# uart.net
KiCad netlist of a schematic drawn in Altium Designer
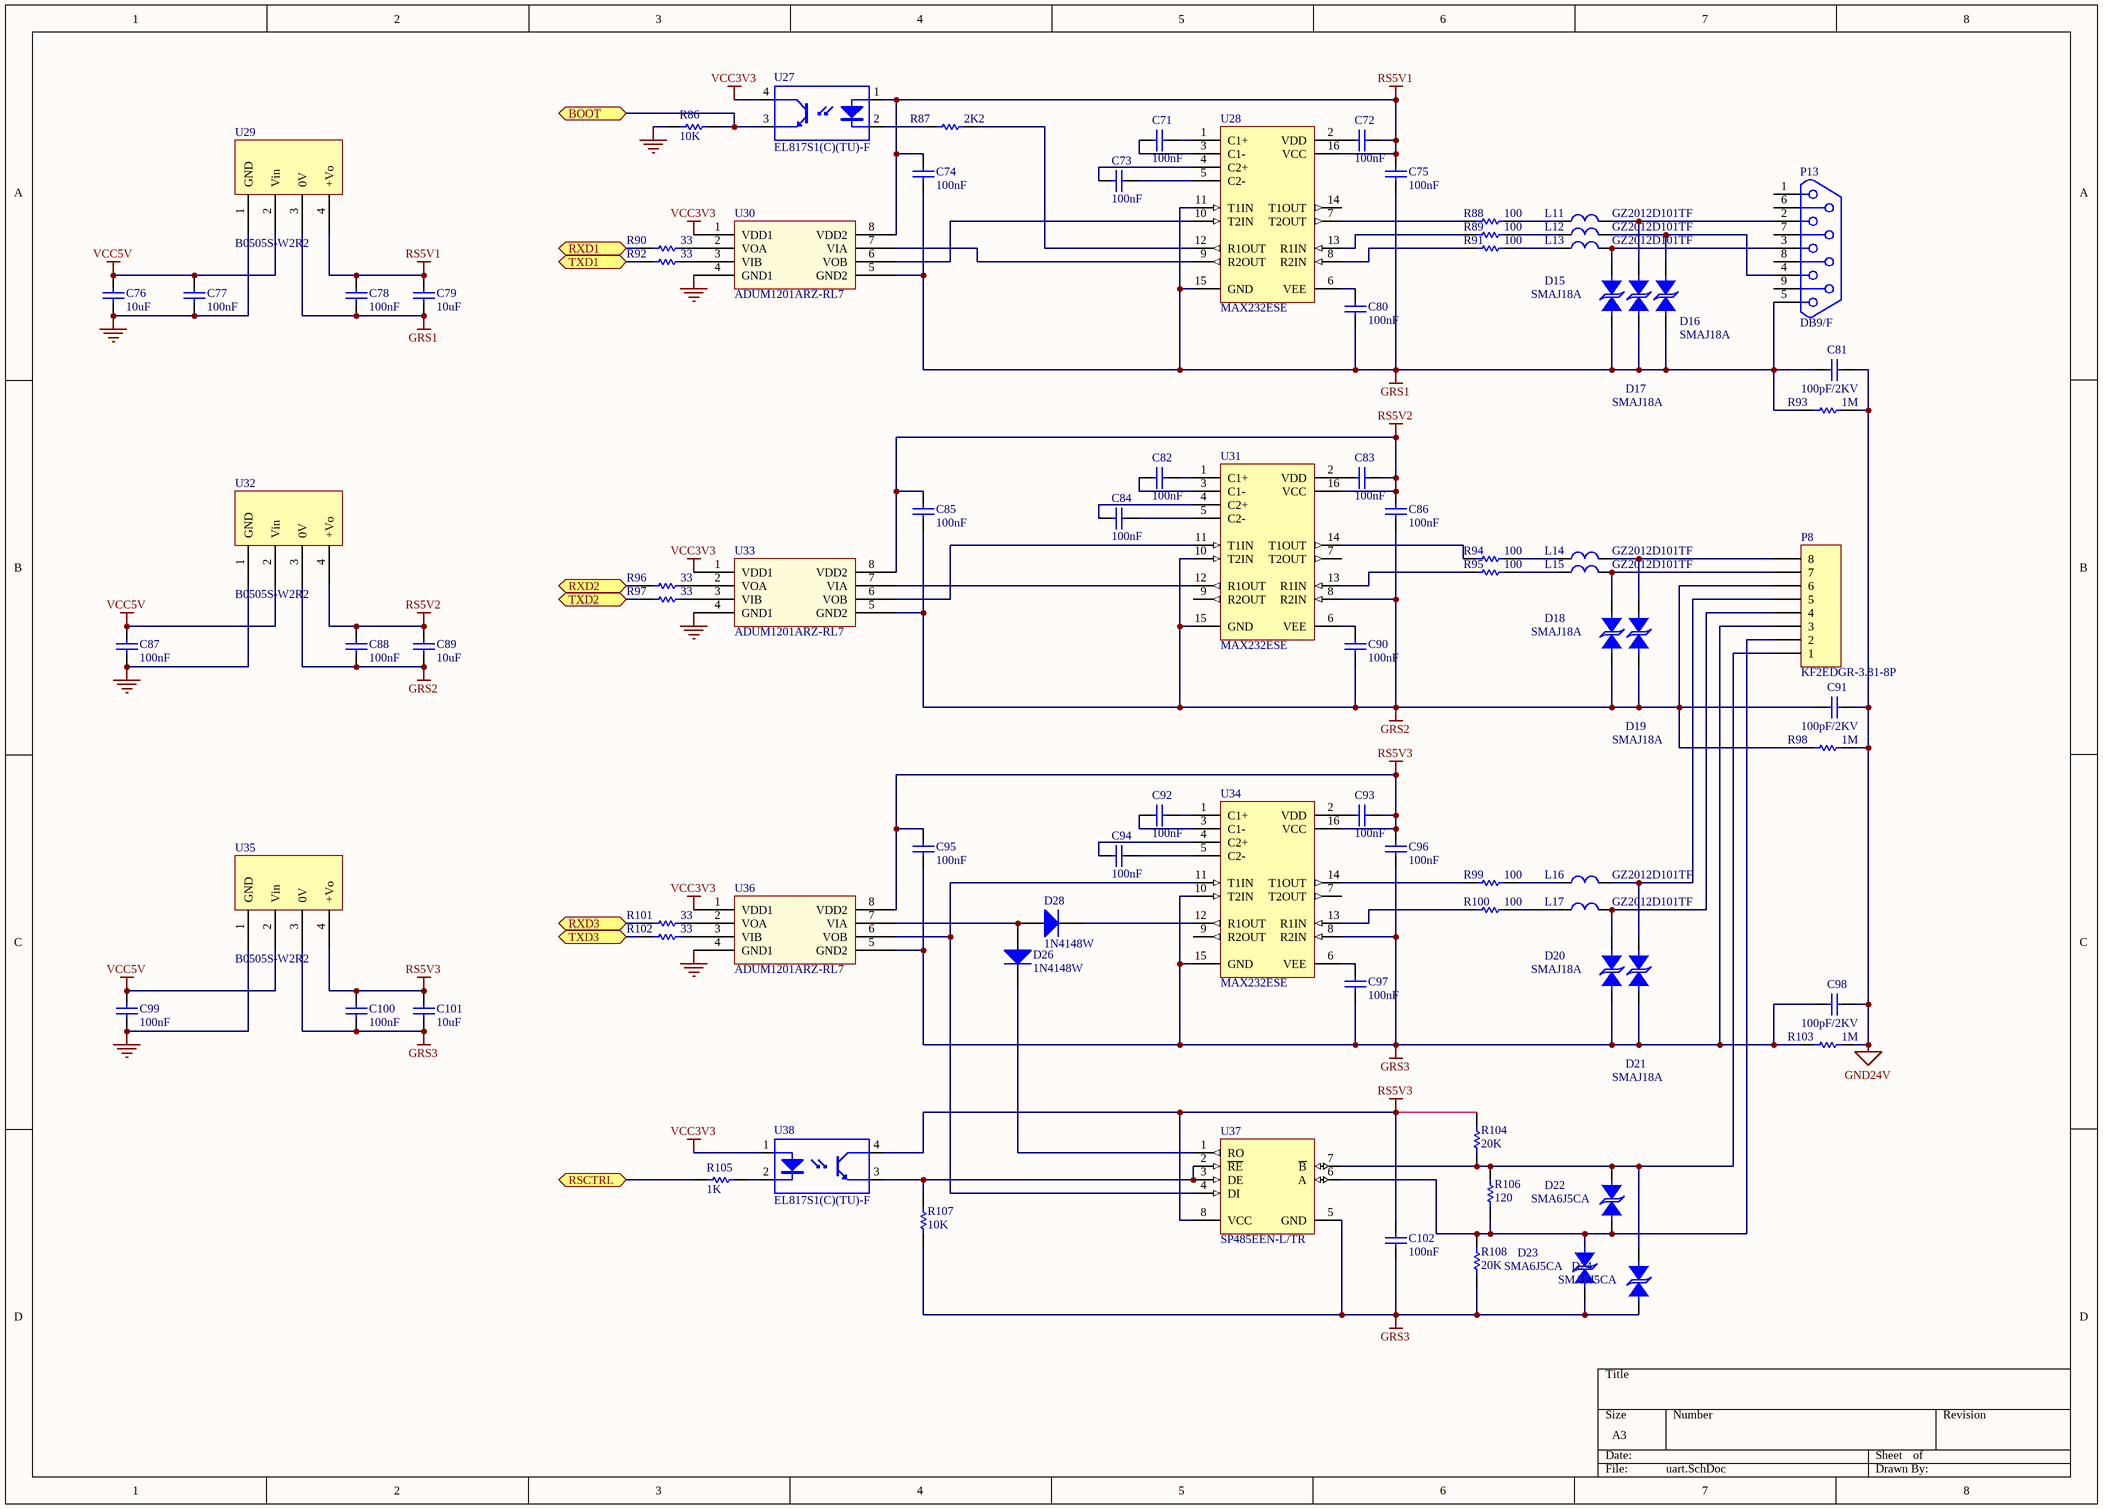
[diagram p0: uart.SchDoc]

(export (version "E")
  (design (tool "Eeschema 10.0.6"))
  (components
    (comp (ref "C71")
      (value "100nF")
      (footprint "0805_C")
      (description "贴片电容")
      (libsource (lib "Miscellaneous Devices LC") (part "0805 100nF(104) 10% 50V"))
    )
    (comp (ref "C72")
      (value "100nF")
      (footprint "0805_C")
      (description "贴片电容")
      (libsource (lib "Miscellaneous Devices LC") (part "0805 100nF(104) 10% 50V"))
    )
    (comp (ref "C73")
      (value "100nF")
      (footprint "0805_C")
      (description "贴片电容")
      (libsource (lib "Miscellaneous Devices LC") (part "0805 100nF(104) 10% 50V"))
    )
    (comp (ref "C74")
      (value "100nF")
      (footprint "0805_C")
      (description "贴片电容")
      (libsource (lib "Miscellaneous Devices LC") (part "0805 100nF(104) 10% 50V"))
    )
    (comp (ref "C75")
      (value "100nF")
      (footprint "0805_C")
      (description "贴片电容")
      (libsource (lib "Miscellaneous Devices LC") (part "0805 100nF(104) 10% 50V"))
    )
    (comp (ref "C76")
      (value "10uF")
      (footprint "0805_C")
      (description "贴片电容")
      (libsource (lib "Miscellaneous Devices LC") (part "0805 10uF (106) 10% 25V"))
    )
    (comp (ref "C77")
      (value "100nF")
      (footprint "0805_C")
      (description "贴片电容")
      (libsource (lib "Miscellaneous Devices LC") (part "0805 100nF(104) 10% 50V"))
    )
    (comp (ref "C78")
      (value "100nF")
      (footprint "0805_C")
      (description "贴片电容")
      (libsource (lib "Miscellaneous Devices LC") (part "0805 100nF(104) 10% 50V"))
    )
    (comp (ref "C79")
      (value "10uF")
      (footprint "0805_C")
      (description "贴片电容")
      (libsource (lib "Miscellaneous Devices LC") (part "0805 10uF (106) 10% 25V"))
    )
    (comp (ref "C80")
      (value "100nF")
      (footprint "0805_C")
      (description "贴片电容")
      (libsource (lib "Miscellaneous Devices LC") (part "0805 100nF(104) 10% 50V"))
    )
    (comp (ref "C81")
      (value "100pF/2KV")
      (footprint "1206_C")
      (description "Capacitor")
      (fields (field (name "PUBLISHER") "Altium Limited"))
      (libsource (lib "Miscellaneous Devices") (part "Cap"))
    )
    (comp (ref "C82")
      (value "100nF")
      (footprint "0805_C")
      (description "贴片电容")
      (libsource (lib "Miscellaneous Devices LC") (part "0805 100nF(104) 10% 50V"))
    )
    (comp (ref "C83")
      (value "100nF")
      (footprint "0805_C")
      (description "贴片电容")
      (libsource (lib "Miscellaneous Devices LC") (part "0805 100nF(104) 10% 50V"))
    )
    (comp (ref "C84")
      (value "100nF")
      (footprint "0805_C")
      (description "贴片电容")
      (libsource (lib "Miscellaneous Devices LC") (part "0805 100nF(104) 10% 50V"))
    )
    (comp (ref "C85")
      (value "100nF")
      (footprint "0805_C")
      (description "贴片电容")
      (libsource (lib "Miscellaneous Devices LC") (part "0805 100nF(104) 10% 50V"))
    )
    (comp (ref "C86")
      (value "100nF")
      (footprint "0805_C")
      (description "贴片电容")
      (libsource (lib "Miscellaneous Devices LC") (part "0805 100nF(104) 10% 50V"))
    )
    (comp (ref "C87")
      (value "100nF")
      (footprint "0805_C")
      (description "贴片电容")
      (libsource (lib "Miscellaneous Devices LC") (part "0805 100nF(104) 10% 50V"))
    )
    (comp (ref "C88")
      (value "100nF")
      (footprint "0805_C")
      (description "贴片电容")
      (libsource (lib "Miscellaneous Devices LC") (part "0805 100nF(104) 10% 50V"))
    )
    (comp (ref "C89")
      (value "10uF")
      (footprint "0805_C")
      (description "贴片电容")
      (libsource (lib "Miscellaneous Devices LC") (part "0805 10uF (106) 10% 25V"))
    )
    (comp (ref "C90")
      (value "100nF")
      (footprint "0805_C")
      (description "贴片电容")
      (libsource (lib "Miscellaneous Devices LC") (part "0805 100nF(104) 10% 50V"))
    )
    (comp (ref "C91")
      (value "100pF/2KV")
      (footprint "1206_C")
      (description "Capacitor")
      (fields (field (name "PUBLISHER") "Altium Limited"))
      (libsource (lib "Miscellaneous Devices") (part "Cap"))
    )
    (comp (ref "C92")
      (value "100nF")
      (footprint "0805_C")
      (description "贴片电容")
      (libsource (lib "Miscellaneous Devices LC") (part "0805 100nF(104) 10% 50V"))
    )
    (comp (ref "C93")
      (value "100nF")
      (footprint "0805_C")
      (description "贴片电容")
      (libsource (lib "Miscellaneous Devices LC") (part "0805 100nF(104) 10% 50V"))
    )
    (comp (ref "C94")
      (value "100nF")
      (footprint "0805_C")
      (description "贴片电容")
      (libsource (lib "Miscellaneous Devices LC") (part "0805 100nF(104) 10% 50V"))
    )
    (comp (ref "C95")
      (value "100nF")
      (footprint "0805_C")
      (description "贴片电容")
      (libsource (lib "Miscellaneous Devices LC") (part "0805 100nF(104) 10% 50V"))
    )
    (comp (ref "C96")
      (value "100nF")
      (footprint "0805_C")
      (description "贴片电容")
      (libsource (lib "Miscellaneous Devices LC") (part "0805 100nF(104) 10% 50V"))
    )
    (comp (ref "C97")
      (value "100nF")
      (footprint "0805_C")
      (description "贴片电容")
      (libsource (lib "Miscellaneous Devices LC") (part "0805 100nF(104) 10% 50V"))
    )
    (comp (ref "C98")
      (value "100pF/2KV")
      (footprint "1206_C")
      (description "Capacitor")
      (fields (field (name "PUBLISHER") "Altium Limited"))
      (libsource (lib "Miscellaneous Devices") (part "Cap"))
    )
    (comp (ref "C99")
      (value "100nF")
      (footprint "0805_C")
      (description "贴片电容")
      (libsource (lib "Miscellaneous Devices LC") (part "0805 100nF(104) 10% 50V"))
    )
    (comp (ref "C100")
      (value "100nF")
      (footprint "0805_C")
      (description "贴片电容")
      (libsource (lib "Miscellaneous Devices LC") (part "0805 100nF(104) 10% 50V"))
    )
    (comp (ref "C101")
      (value "10uF")
      (footprint "0805_C")
      (description "贴片电容")
      (libsource (lib "Miscellaneous Devices LC") (part "0805 10uF (106) 10% 25V"))
    )
    (comp (ref "C102")
      (value "100nF")
      (footprint "0805_C")
      (description "贴片电容")
      (libsource (lib "Miscellaneous Devices LC") (part "0805 100nF(104) 10% 50V"))
    )
    (comp (ref "D15")
      (value "SMAJ18A")
      (footprint "SMA")
      (description "1V5KE6V8CA")
      (libsource (lib "Schlib1") (part "Bidirectional DIODE TVS"))
    )
    (comp (ref "D16")
      (value "SMAJ18A")
      (footprint "SMA")
      (description "1V5KE6V8CA")
      (libsource (lib "Schlib1") (part "Bidirectional DIODE TVS"))
    )
    (comp (ref "D17")
      (value "SMAJ18A")
      (footprint "SMA")
      (description "1V5KE6V8CA")
      (libsource (lib "Schlib1") (part "Bidirectional DIODE TVS"))
    )
    (comp (ref "D18")
      (value "SMAJ18A")
      (footprint "SMA")
      (description "1V5KE6V8CA")
      (libsource (lib "Schlib1") (part "Bidirectional DIODE TVS"))
    )
    (comp (ref "D19")
      (value "SMAJ18A")
      (footprint "SMA")
      (description "1V5KE6V8CA")
      (libsource (lib "Schlib1") (part "Bidirectional DIODE TVS"))
    )
    (comp (ref "D20")
      (value "SMAJ18A")
      (footprint "SMA")
      (description "1V5KE6V8CA")
      (libsource (lib "Schlib1") (part "Bidirectional DIODE TVS"))
    )
    (comp (ref "D21")
      (value "SMAJ18A")
      (footprint "SMA")
      (description "1V5KE6V8CA")
      (libsource (lib "Schlib1") (part "Bidirectional DIODE TVS"))
    )
    (comp (ref "D22")
      (value "SMA6J5CA")
      (footprint "SMA")
      (description "1V5KE6V8CA")
      (libsource (lib "Schlib1") (part "Bidirectional DIODE TVS"))
    )
    (comp (ref "D23")
      (value "SMA6J5CA")
      (footprint "SMA")
      (description "1V5KE6V8CA")
      (libsource (lib "Schlib1") (part "Bidirectional DIODE TVS"))
    )
    (comp (ref "D24")
      (value "SMA6J5CA")
      (footprint "SMA")
      (description "1V5KE6V8CA")
      (libsource (lib "Schlib1") (part "Bidirectional DIODE TVS"))
    )
    (comp (ref "D26")
      (value "1N4148W")
      (footprint "SOD-123")
      (description "Default Diode")
      (fields (field (name "PUBLISHER") "Altium Limited"))
      (libsource (lib "Miscellaneous Devices") (part "Diode"))
    )
    (comp (ref "D28")
      (value "1N4148W")
      (footprint "SOD-123")
      (description "Default Diode")
      (fields (field (name "PUBLISHER") "Altium Limited"))
      (libsource (lib "Miscellaneous Devices") (part "Diode"))
    )
    (comp (ref "L11") (value "GZ2012D101TF") (footprint "0805_L") (libsource (lib "Devices") (part "L1")))
    (comp (ref "L12") (value "GZ2012D101TF") (footprint "0805_L") (libsource (lib "Devices") (part "L1")))
    (comp (ref "L13") (value "GZ2012D101TF") (footprint "0805_L") (libsource (lib "Devices") (part "L1")))
    (comp (ref "L14") (value "GZ2012D101TF") (footprint "0805_L") (libsource (lib "Devices") (part "L1")))
    (comp (ref "L15") (value "GZ2012D101TF") (footprint "0805_L") (libsource (lib "Devices") (part "L1")))
    (comp (ref "L16") (value "GZ2012D101TF") (footprint "0805_L") (libsource (lib "Devices") (part "L1")))
    (comp (ref "L17") (value "GZ2012D101TF") (footprint "0805_L") (libsource (lib "Devices") (part "L1")))
    (comp (ref "P8")
      (value "KF2EDGR-3.81-8P")
      (footprint "MC1.5/8-ST-3.81")
      (description "Header, 8-Pin")
      (fields (field (name "PUBLISHER") "Altium Limited"))
      (libsource (lib "Miscellaneous Connectors") (part "Header 8"))
    )
    (comp (ref "P13") (value "DB9/F") (footprint "DB9P/F") (libsource (lib "Devices") (part "DB9")))
    (comp (ref "R86")
      (value "10K")
      (footprint "0805_R")
      (description "Resistor")
      (fields (field (name "PUBLISHER") "Altium Limited"))
      (libsource (lib "Miscellaneous Devices") (part "Res1"))
    )
    (comp (ref "R87")
      (value "2K2")
      (footprint "0805_R")
      (description "Resistor")
      (fields (field (name "PUBLISHER") "Altium Limited"))
      (libsource (lib "Miscellaneous Devices") (part "Res1"))
    )
    (comp (ref "R88")
      (value "100")
      (footprint "0805_R")
      (description "Resistor")
      (fields (field (name "PUBLISHER") "Altium Limited"))
      (libsource (lib "Miscellaneous Devices") (part "Res1"))
    )
    (comp (ref "R89")
      (value "100")
      (footprint "0805_R")
      (description "Resistor")
      (fields (field (name "PUBLISHER") "Altium Limited"))
      (libsource (lib "Miscellaneous Devices") (part "Res1"))
    )
    (comp (ref "R90")
      (value "33")
      (footprint "0805_R")
      (description "Resistor")
      (fields (field (name "PUBLISHER") "Altium Limited"))
      (libsource (lib "Miscellaneous Devices") (part "Res1"))
    )
    (comp (ref "R91")
      (value "100")
      (footprint "0805_R")
      (description "Resistor")
      (fields (field (name "PUBLISHER") "Altium Limited"))
      (libsource (lib "Miscellaneous Devices") (part "Res1"))
    )
    (comp (ref "R92")
      (value "33")
      (footprint "0805_R")
      (description "Resistor")
      (fields (field (name "PUBLISHER") "Altium Limited"))
      (libsource (lib "Miscellaneous Devices") (part "Res1"))
    )
    (comp (ref "R93")
      (value "1M")
      (footprint "1206_R")
      (description "Resistor")
      (fields (field (name "PUBLISHER") "Altium Limited"))
      (libsource (lib "Miscellaneous Devices") (part "Res1"))
    )
    (comp (ref "R94")
      (value "100")
      (footprint "0805_R")
      (description "Resistor")
      (fields (field (name "PUBLISHER") "Altium Limited"))
      (libsource (lib "Miscellaneous Devices") (part "Res1"))
    )
    (comp (ref "R95")
      (value "100")
      (footprint "0805_R")
      (description "Resistor")
      (fields (field (name "PUBLISHER") "Altium Limited"))
      (libsource (lib "Miscellaneous Devices") (part "Res1"))
    )
    (comp (ref "R96")
      (value "33")
      (footprint "0805_R")
      (description "Resistor")
      (fields (field (name "PUBLISHER") "Altium Limited"))
      (libsource (lib "Miscellaneous Devices") (part "Res1"))
    )
    (comp (ref "R97")
      (value "33")
      (footprint "0805_R")
      (description "Resistor")
      (fields (field (name "PUBLISHER") "Altium Limited"))
      (libsource (lib "Miscellaneous Devices") (part "Res1"))
    )
    (comp (ref "R98")
      (value "1M")
      (footprint "1206_R")
      (description "Resistor")
      (fields (field (name "PUBLISHER") "Altium Limited"))
      (libsource (lib "Miscellaneous Devices") (part "Res1"))
    )
    (comp (ref "R99")
      (value "100")
      (footprint "0805_R")
      (description "Resistor")
      (fields (field (name "PUBLISHER") "Altium Limited"))
      (libsource (lib "Miscellaneous Devices") (part "Res1"))
    )
    (comp (ref "R100")
      (value "100")
      (footprint "0805_R")
      (description "Resistor")
      (fields (field (name "PUBLISHER") "Altium Limited"))
      (libsource (lib "Miscellaneous Devices") (part "Res1"))
    )
    (comp (ref "R101")
      (value "33")
      (footprint "0805_R")
      (description "Resistor")
      (fields (field (name "PUBLISHER") "Altium Limited"))
      (libsource (lib "Miscellaneous Devices") (part "Res1"))
    )
    (comp (ref "R102")
      (value "33")
      (footprint "0805_R")
      (description "Resistor")
      (fields (field (name "PUBLISHER") "Altium Limited"))
      (libsource (lib "Miscellaneous Devices") (part "Res1"))
    )
    (comp (ref "R103")
      (value "1M")
      (footprint "1206_R")
      (description "Resistor")
      (fields (field (name "PUBLISHER") "Altium Limited"))
      (libsource (lib "Miscellaneous Devices") (part "Res1"))
    )
    (comp (ref "R104")
      (value "20K")
      (footprint "0805_R")
      (description "Resistor")
      (fields (field (name "PUBLISHER") "Altium Limited"))
      (libsource (lib "Miscellaneous Devices") (part "Res1"))
    )
    (comp (ref "R105")
      (value "1K")
      (footprint "0805_R")
      (description "Resistor")
      (fields (field (name "PUBLISHER") "Altium Limited"))
      (libsource (lib "Miscellaneous Devices") (part "Res1"))
    )
    (comp (ref "R106")
      (value "120")
      (footprint "0805_R")
      (description "Resistor")
      (fields (field (name "PUBLISHER") "Altium Limited"))
      (libsource (lib "Miscellaneous Devices") (part "Res1"))
    )
    (comp (ref "R107")
      (value "10K")
      (footprint "0805_R")
      (description "Resistor")
      (fields (field (name "PUBLISHER") "Altium Limited"))
      (libsource (lib "Miscellaneous Devices") (part "Res1"))
    )
    (comp (ref "R108")
      (value "20K")
      (footprint "0805_R")
      (description "Resistor")
      (fields (field (name "PUBLISHER") "Altium Limited"))
      (libsource (lib "Miscellaneous Devices") (part "Res1"))
    )
    (comp (ref "U27")
      (value "EL817S1(C)(TU)-F")
      (footprint "LC-SMD-4")
      (libsource (lib "IC") (part "TLP521"))
    )
    (comp (ref "U28")
      (value "MAX232ESE")
      (footprint "SOIC-16_150mil")
      (description "RS232")
      (libsource (lib "Miscellaneous Devices LC") (part "MAX232ESE_[C26860]"))
    )
    (comp (ref "U29")
      (value "B0505S-W2R2")
      (footprint "MORNSUN-BM")
      (description "MORNSUN Fixed input,Isolated,Unregulated Series DC/DC")
      (libsource (lib "稳压器件") (part "MORNSUN-BM"))
    )
    (comp (ref "U30")
      (value "ADUM1201ARZ-RL7")
      (footprint "SOIC-8_150mil")
      (description "隔离器")
      (libsource (lib "IC") (part "ADUM1201ARZ-RL7_[C9669]"))
    )
    (comp (ref "U31")
      (value "MAX232ESE")
      (footprint "SOIC-16_150mil")
      (description "RS232")
      (libsource (lib "Miscellaneous Devices LC") (part "MAX232ESE_[C26860]"))
    )
    (comp (ref "U32")
      (value "B0505S-W2R2")
      (footprint "MORNSUN-BM")
      (description "MORNSUN Fixed input,Isolated,Unregulated Series DC/DC")
      (libsource (lib "稳压器件") (part "MORNSUN-BM"))
    )
    (comp (ref "U33")
      (value "ADUM1201ARZ-RL7")
      (footprint "SOIC-8_150mil")
      (description "隔离器")
      (libsource (lib "IC") (part "ADUM1201ARZ-RL7_[C9669]"))
    )
    (comp (ref "U34")
      (value "MAX232ESE")
      (footprint "SOIC-16_150mil")
      (description "RS232")
      (libsource (lib "Miscellaneous Devices LC") (part "MAX232ESE_[C26860]"))
    )
    (comp (ref "U35")
      (value "B0505S-W2R2")
      (footprint "MORNSUN-BM")
      (description "MORNSUN Fixed input,Isolated,Unregulated Series DC/DC")
      (libsource (lib "稳压器件") (part "MORNSUN-BM"))
    )
    (comp (ref "U36")
      (value "ADUM1201ARZ-RL7")
      (footprint "SOIC-8_150mil")
      (description "隔离器")
      (libsource (lib "IC") (part "ADUM1201ARZ-RL7_[C9669]"))
    )
    (comp (ref "U37")
      (value "SP485EEN-L/TR")
      (footprint "SOIC-8_150mil")
      (description "RS-485/RS-422")
      (libsource (lib "Miscellaneous Devices LC") (part "SP485EEN-L/TR_[C6855]"))
    )
    (comp (ref "U38")
      (value "EL817S1(C)(TU)-F")
      (footprint "LC-SMD-4")
      (libsource (lib "") (part "TLP521_1"))
    )
  )
  (nets
    (net (code "1") (name "/BOOT") (class "Default")
      (node (ref "R86") (pin "2") (pinfunction "2_2") (pintype "passive"))
      (node (ref "U27") (pin "3") (pinfunction "E_3") (pintype "passive"))
    )
    (net (code "2") (name "/RSCTRL") (class "Default")
      (node (ref "R105") (pin "1") (pinfunction "1_1") (pintype "passive"))
    )
    (net (code "3") (name "/RXD1") (class "Default")
      (node (ref "R90") (pin "1") (pinfunction "1_1") (pintype "passive"))
    )
    (net (code "4") (name "/RXD2") (class "Default")
      (node (ref "R96") (pin "1") (pinfunction "1_1") (pintype "passive"))
    )
    (net (code "5") (name "/RXD3") (class "Default")
      (node (ref "R101") (pin "1") (pinfunction "1_1") (pintype "passive"))
    )
    (net (code "6") (name "/TXD1") (class "Default")
      (node (ref "R92") (pin "2") (pinfunction "2_2") (pintype "passive"))
    )
    (net (code "7") (name "/TXD2") (class "Default")
      (node (ref "R97") (pin "2") (pinfunction "2_2") (pintype "passive"))
    )
    (net (code "8") (name "/TXD3") (class "Default")
      (node (ref "R102") (pin "2") (pinfunction "2_2") (pintype "passive"))
    )
    (net (code "9") (name "GND") (class "Default")
      (node (ref "C76") (pin "1") (pinfunction "1_1") (pintype "passive"))
      (node (ref "C77") (pin "2") (pinfunction "2_2") (pintype "passive"))
      (node (ref "C87") (pin "2") (pinfunction "2_2") (pintype "passive"))
      (node (ref "C99") (pin "2") (pinfunction "2_2") (pintype "passive"))
      (node (ref "R86") (pin "1") (pinfunction "1_1") (pintype "passive"))
      (node (ref "U29") (pin "1") (pinfunction "GND_1") (pintype "passive"))
      (node (ref "U30") (pin "4") (pinfunction "GND1_4") (pintype "passive"))
      (node (ref "U32") (pin "1") (pinfunction "GND_1") (pintype "passive"))
      (node (ref "U33") (pin "4") (pinfunction "GND1_4") (pintype "passive"))
      (node (ref "U35") (pin "1") (pinfunction "GND_1") (pintype "passive"))
      (node (ref "U36") (pin "4") (pinfunction "GND1_4") (pintype "passive"))
    )
    (net (code "10") (name "GND24V") (class "Default")
      (node (ref "C81") (pin "2") (pinfunction "2_2") (pintype "passive"))
      (node (ref "C91") (pin "2") (pinfunction "2_2") (pintype "passive"))
      (node (ref "C98") (pin "2") (pinfunction "2_2") (pintype "passive"))
      (node (ref "R103") (pin "2") (pinfunction "2_2") (pintype "passive"))
      (node (ref "R93") (pin "2") (pinfunction "2_2") (pintype "passive"))
      (node (ref "R98") (pin "2") (pinfunction "2_2") (pintype "passive"))
    )
    (net (code "11") (name "GRS1") (class "Default")
      (node (ref "C74") (pin "2") (pinfunction "2_2") (pintype "passive"))
      (node (ref "C75") (pin "2") (pinfunction "2_2") (pintype "passive"))
      (node (ref "C78") (pin "2") (pinfunction "2_2") (pintype "passive"))
      (node (ref "C79") (pin "1") (pinfunction "1_1") (pintype "passive"))
      (node (ref "C80") (pin "1") (pinfunction "1_1") (pintype "passive"))
      (node (ref "C81") (pin "1") (pinfunction "1_1") (pintype "passive"))
      (node (ref "D15") (pin "1") (pinfunction "ANODE_1") (pintype "passive"))
      (node (ref "D16") (pin "1") (pinfunction "ANODE_1") (pintype "passive"))
      (node (ref "D17") (pin "1") (pinfunction "ANODE_1") (pintype "passive"))
      (node (ref "P13") (pin "5") (pinfunction "5_5") (pintype "passive"))
      (node (ref "R93") (pin "1") (pinfunction "1_1") (pintype "passive"))
      (node (ref "U28") (pin "11") (pinfunction "T1IN_11") (pintype "input"))
      (node (ref "U28") (pin "15") (pinfunction "GND_15") (pintype "power_in"))
      (node (ref "U29") (pin "3") (pinfunction "0V_3") (pintype "passive"))
      (node (ref "U30") (pin "5") (pinfunction "GND2_5") (pintype "passive"))
    )
    (net (code "12") (name "GRS2") (class "Default")
      (node (ref "C85") (pin "2") (pinfunction "2_2") (pintype "passive"))
      (node (ref "C86") (pin "2") (pinfunction "2_2") (pintype "passive"))
      (node (ref "C88") (pin "2") (pinfunction "2_2") (pintype "passive"))
      (node (ref "C89") (pin "1") (pinfunction "1_1") (pintype "passive"))
      (node (ref "C90") (pin "1") (pinfunction "1_1") (pintype "passive"))
      (node (ref "C91") (pin "1") (pinfunction "1_1") (pintype "passive"))
      (node (ref "D18") (pin "1") (pinfunction "ANODE_1") (pintype "passive"))
      (node (ref "D19") (pin "1") (pinfunction "ANODE_1") (pintype "passive"))
      (node (ref "P8") (pin "6") (pinfunction "6_6") (pintype "passive"))
      (node (ref "R98") (pin "1") (pinfunction "1_1") (pintype "passive"))
      (node (ref "U31") (pin "10") (pinfunction "T2IN_10") (pintype "input"))
      (node (ref "U31") (pin "15") (pinfunction "GND_15") (pintype "power_in"))
      (node (ref "U31") (pin "8") (pinfunction "R2IN_8") (pintype "input"))
      (node (ref "U32") (pin "3") (pinfunction "0V_3") (pintype "passive"))
      (node (ref "U33") (pin "5") (pinfunction "GND2_5") (pintype "passive"))
    )
    (net (code "13") (name "GRS3") (class "Default")
      (node (ref "C100") (pin "2") (pinfunction "2_2") (pintype "passive"))
      (node (ref "C101") (pin "1") (pinfunction "1_1") (pintype "passive"))
      (node (ref "C102") (pin "1") (pinfunction "1_1") (pintype "passive"))
      (node (ref "C95") (pin "2") (pinfunction "2_2") (pintype "passive"))
      (node (ref "C96") (pin "2") (pinfunction "2_2") (pintype "passive"))
      (node (ref "C97") (pin "1") (pinfunction "1_1") (pintype "passive"))
      (node (ref "C98") (pin "1") (pinfunction "1_1") (pintype "passive"))
      (node (ref "D20") (pin "1") (pinfunction "ANODE_1") (pintype "passive"))
      (node (ref "D21") (pin "1") (pinfunction "ANODE_1") (pintype "passive"))
      (node (ref "D23") (pin "1") (pinfunction "ANODE_1") (pintype "passive"))
      (node (ref "D24") (pin "1") (pinfunction "ANODE_1") (pintype "passive"))
      (node (ref "P8") (pin "3") (pinfunction "3_3") (pintype "passive"))
      (node (ref "R103") (pin "1") (pinfunction "1_1") (pintype "passive"))
      (node (ref "R107") (pin "2") (pinfunction "2_2") (pintype "passive"))
      (node (ref "R108") (pin "2") (pinfunction "2_2") (pintype "passive"))
      (node (ref "U34") (pin "10") (pinfunction "T2IN_10") (pintype "input"))
      (node (ref "U34") (pin "15") (pinfunction "GND_15") (pintype "power_in"))
      (node (ref "U34") (pin "8") (pinfunction "R2IN_8") (pintype "input"))
      (node (ref "U35") (pin "3") (pinfunction "0V_3") (pintype "passive"))
      (node (ref "U36") (pin "5") (pinfunction "GND2_5") (pintype "passive"))
      (node (ref "U37") (pin "5") (pinfunction "GND_5") (pintype "power_in"))
    )
    (net (code "14") (name "Net-(D15-CATHODE)") (class "Default")
      (node (ref "D15") (pin "2") (pinfunction "CATHODE_2") (pintype "passive"))
      (node (ref "L13") (pin "2") (pinfunction "2_2") (pintype "passive"))
      (node (ref "P13") (pin "3") (pinfunction "3_3") (pintype "passive"))
    )
    (net (code "15") (name "Net-(D16-CATHODE)") (class "Default")
      (node (ref "D16") (pin "2") (pinfunction "CATHODE_2") (pintype "passive"))
      (node (ref "L12") (pin "2") (pinfunction "2_2") (pintype "passive"))
      (node (ref "P13") (pin "4") (pinfunction "4_4") (pintype "passive"))
    )
    (net (code "16") (name "Net-(D17-CATHODE)") (class "Default")
      (node (ref "D17") (pin "2") (pinfunction "CATHODE_2") (pintype "passive"))
      (node (ref "L11") (pin "2") (pinfunction "2_2") (pintype "passive"))
      (node (ref "P13") (pin "2") (pinfunction "2_2") (pintype "passive"))
    )
    (net (code "17") (name "Net-(D18-CATHODE)") (class "Default")
      (node (ref "D18") (pin "2") (pinfunction "CATHODE_2") (pintype "passive"))
      (node (ref "L15") (pin "2") (pinfunction "2_2") (pintype "passive"))
      (node (ref "P8") (pin "7") (pinfunction "7_7") (pintype "passive"))
    )
    (net (code "18") (name "Net-(D19-CATHODE)") (class "Default")
      (node (ref "D19") (pin "2") (pinfunction "CATHODE_2") (pintype "passive"))
      (node (ref "L14") (pin "2") (pinfunction "2_2") (pintype "passive"))
      (node (ref "P8") (pin "8") (pinfunction "8_8") (pintype "passive"))
    )
    (net (code "19") (name "Net-(D20-CATHODE)") (class "Default")
      (node (ref "D20") (pin "2") (pinfunction "CATHODE_2") (pintype "passive"))
      (node (ref "L17") (pin "2") (pinfunction "2_2") (pintype "passive"))
      (node (ref "P8") (pin "4") (pinfunction "4_4") (pintype "passive"))
    )
    (net (code "20") (name "Net-(D21-CATHODE)") (class "Default")
      (node (ref "D21") (pin "2") (pinfunction "CATHODE_2") (pintype "passive"))
      (node (ref "L16") (pin "2") (pinfunction "2_2") (pintype "passive"))
      (node (ref "P8") (pin "5") (pinfunction "5_5") (pintype "passive"))
    )
    (net (code "21") (name "Net-(D22-ANODE)") (class "Default")
      (node (ref "D22") (pin "1") (pinfunction "ANODE_1") (pintype "passive"))
      (node (ref "D23") (pin "2") (pinfunction "CATHODE_2") (pintype "passive"))
      (node (ref "P8") (pin "2") (pinfunction "2_2") (pintype "passive"))
      (node (ref "R106") (pin "2") (pinfunction "2_2") (pintype "passive"))
      (node (ref "R108") (pin "1") (pinfunction "1_1") (pintype "passive"))
      (node (ref "U37") (pin "6") (pinfunction "A_6") (pintype "bidirectional"))
    )
    (net (code "22") (name "Net-(D22-CATHODE)") (class "Default")
      (node (ref "D22") (pin "2") (pinfunction "CATHODE_2") (pintype "passive"))
      (node (ref "D24") (pin "2") (pinfunction "CATHODE_2") (pintype "passive"))
      (node (ref "P8") (pin "1") (pinfunction "1_1") (pintype "passive"))
      (node (ref "R104") (pin "2") (pinfunction "2_2") (pintype "passive"))
      (node (ref "R106") (pin "1") (pinfunction "1_1") (pintype "passive"))
      (node (ref "U37") (pin "7") (pinfunction "~{B}_7") (pintype "bidirectional"))
    )
    (net (code "23") (name "Net-(D26-A)") (class "Default")
      (node (ref "D26") (pin "1") (pinfunction "A_1") (pintype "passive"))
      (node (ref "D28") (pin "1") (pinfunction "A_1") (pintype "passive"))
      (node (ref "U36") (pin "7") (pinfunction "VIA_7") (pintype "passive"))
    )
    (net (code "24") (name "Net-(D26-K)") (class "Default")
      (node (ref "D26") (pin "2") (pinfunction "K_2") (pintype "passive"))
      (node (ref "U37") (pin "1") (pinfunction "RO_1") (pintype "output"))
    )
    (net (code "25") (name "Net-(D28-K)") (class "Default")
      (node (ref "D28") (pin "2") (pinfunction "K_2") (pintype "passive"))
      (node (ref "U34") (pin "12") (pinfunction "R1OUT_12") (pintype "output"))
    )
    (net (code "26") (name "Net-(L11-Pad1)") (class "Default")
      (node (ref "L11") (pin "1") (pinfunction "1_1") (pintype "passive"))
      (node (ref "R88") (pin "1") (pinfunction "1_1") (pintype "passive"))
    )
    (net (code "27") (name "Net-(L12-Pad1)") (class "Default")
      (node (ref "L12") (pin "1") (pinfunction "1_1") (pintype "passive"))
      (node (ref "R89") (pin "1") (pinfunction "1_1") (pintype "passive"))
    )
    (net (code "28") (name "Net-(L13-Pad1)") (class "Default")
      (node (ref "L13") (pin "1") (pinfunction "1_1") (pintype "passive"))
      (node (ref "R91") (pin "1") (pinfunction "1_1") (pintype "passive"))
    )
    (net (code "29") (name "Net-(L14-Pad1)") (class "Default")
      (node (ref "L14") (pin "1") (pinfunction "1_1") (pintype "passive"))
      (node (ref "R94") (pin "1") (pinfunction "1_1") (pintype "passive"))
    )
    (net (code "30") (name "Net-(L15-Pad1)") (class "Default")
      (node (ref "L15") (pin "1") (pinfunction "1_1") (pintype "passive"))
      (node (ref "R95") (pin "1") (pinfunction "1_1") (pintype "passive"))
    )
    (net (code "31") (name "Net-(L16-Pad1)") (class "Default")
      (node (ref "L16") (pin "1") (pinfunction "1_1") (pintype "passive"))
      (node (ref "R99") (pin "1") (pinfunction "1_1") (pintype "passive"))
    )
    (net (code "32") (name "Net-(L17-Pad1)") (class "Default")
      (node (ref "L17") (pin "1") (pinfunction "1_1") (pintype "passive"))
      (node (ref "R100") (pin "1") (pinfunction "1_1") (pintype "passive"))
    )
    (net (code "33") (name "Net-(U27-K)") (class "Default")
      (node (ref "R87") (pin "1") (pinfunction "1_1") (pintype "passive"))
      (node (ref "U27") (pin "2") (pinfunction "K_2") (pintype "passive"))
    )
    (net (code "34") (name "Net-(U28-C1+)") (class "Default")
      (node (ref "C71") (pin "1") (pinfunction "1_1") (pintype "passive"))
      (node (ref "U28") (pin "1") (pinfunction "C1+_1") (pintype "passive"))
    )
    (net (code "35") (name "Net-(U28-C1-)") (class "Default")
      (node (ref "C71") (pin "2") (pinfunction "2_2") (pintype "passive"))
      (node (ref "U28") (pin "3") (pinfunction "C1-_3") (pintype "passive"))
    )
    (net (code "36") (name "Net-(U28-C2+)") (class "Default")
      (node (ref "C73") (pin "2") (pinfunction "2_2") (pintype "passive"))
      (node (ref "U28") (pin "4") (pinfunction "C2+_4") (pintype "passive"))
    )
    (net (code "37") (name "Net-(U28-C2-)") (class "Default")
      (node (ref "C73") (pin "1") (pinfunction "1_1") (pintype "passive"))
      (node (ref "U28") (pin "5") (pinfunction "C2-_5") (pintype "passive"))
    )
    (net (code "38") (name "Net-(U28-R1IN)") (class "Default")
      (node (ref "R89") (pin "2") (pinfunction "2_2") (pintype "passive"))
      (node (ref "U28") (pin "13") (pinfunction "R1IN_13") (pintype "input"))
    )
    (net (code "39") (name "Net-(U28-R1OUT)") (class "Default")
      (node (ref "R87") (pin "2") (pinfunction "2_2") (pintype "passive"))
      (node (ref "U28") (pin "12") (pinfunction "R1OUT_12") (pintype "output"))
    )
    (net (code "40") (name "Net-(U28-R2IN)") (class "Default")
      (node (ref "R91") (pin "2") (pinfunction "2_2") (pintype "passive"))
      (node (ref "U28") (pin "8") (pinfunction "R2IN_8") (pintype "input"))
    )
    (net (code "41") (name "Net-(U28-R2OUT)") (class "Default")
      (node (ref "U28") (pin "9") (pinfunction "R2OUT_9") (pintype "output"))
      (node (ref "U30") (pin "7") (pinfunction "VIA_7") (pintype "passive"))
    )
    (net (code "42") (name "Net-(U28-T2IN)") (class "Default")
      (node (ref "U28") (pin "10") (pinfunction "T2IN_10") (pintype "input"))
      (node (ref "U30") (pin "6") (pinfunction "VOB_6") (pintype "passive"))
    )
    (net (code "43") (name "Net-(U28-T2OUT)") (class "Default")
      (node (ref "R88") (pin "2") (pinfunction "2_2") (pintype "passive"))
      (node (ref "U28") (pin "7") (pinfunction "T2OUT_7") (pintype "output"))
    )
    (net (code "44") (name "Net-(U28-VDD)") (class "Default")
      (node (ref "C72") (pin "2") (pinfunction "2_2") (pintype "passive"))
      (node (ref "U28") (pin "2") (pinfunction "VDD_2") (pintype "power_in"))
    )
    (net (code "45") (name "Net-(U28-VEE)") (class "Default")
      (node (ref "C80") (pin "2") (pinfunction "2_2") (pintype "passive"))
      (node (ref "U28") (pin "6") (pinfunction "VEE_6") (pintype "power_in"))
    )
    (net (code "46") (name "Net-(U30-VIB)") (class "Default")
      (node (ref "R92") (pin "1") (pinfunction "1_1") (pintype "passive"))
      (node (ref "U30") (pin "3") (pinfunction "VIB_3") (pintype "passive"))
    )
    (net (code "47") (name "Net-(U30-VOA)") (class "Default")
      (node (ref "R90") (pin "2") (pinfunction "2_2") (pintype "passive"))
      (node (ref "U30") (pin "2") (pinfunction "VOA_2") (pintype "passive"))
    )
    (net (code "48") (name "Net-(U31-C1+)") (class "Default")
      (node (ref "C82") (pin "1") (pinfunction "1_1") (pintype "passive"))
      (node (ref "U31") (pin "1") (pinfunction "C1+_1") (pintype "passive"))
    )
    (net (code "49") (name "Net-(U31-C1-)") (class "Default")
      (node (ref "C82") (pin "2") (pinfunction "2_2") (pintype "passive"))
      (node (ref "U31") (pin "3") (pinfunction "C1-_3") (pintype "passive"))
    )
    (net (code "50") (name "Net-(U31-C2+)") (class "Default")
      (node (ref "C84") (pin "2") (pinfunction "2_2") (pintype "passive"))
      (node (ref "U31") (pin "4") (pinfunction "C2+_4") (pintype "passive"))
    )
    (net (code "51") (name "Net-(U31-C2-)") (class "Default")
      (node (ref "C84") (pin "1") (pinfunction "1_1") (pintype "passive"))
      (node (ref "U31") (pin "5") (pinfunction "C2-_5") (pintype "passive"))
    )
    (net (code "52") (name "Net-(U31-R1IN)") (class "Default")
      (node (ref "R95") (pin "2") (pinfunction "2_2") (pintype "passive"))
      (node (ref "U31") (pin "13") (pinfunction "R1IN_13") (pintype "input"))
    )
    (net (code "53") (name "Net-(U31-R1OUT)") (class "Default")
      (node (ref "U31") (pin "12") (pinfunction "R1OUT_12") (pintype "output"))
      (node (ref "U33") (pin "7") (pinfunction "VIA_7") (pintype "passive"))
    )
    (net (code "54") (name "Net-(U31-T1IN)") (class "Default")
      (node (ref "U31") (pin "11") (pinfunction "T1IN_11") (pintype "input"))
      (node (ref "U33") (pin "6") (pinfunction "VOB_6") (pintype "passive"))
    )
    (net (code "55") (name "Net-(U31-T1OUT)") (class "Default")
      (node (ref "R94") (pin "2") (pinfunction "2_2") (pintype "passive"))
      (node (ref "U31") (pin "14") (pinfunction "T1OUT_14") (pintype "output"))
    )
    (net (code "56") (name "Net-(U31-VDD)") (class "Default")
      (node (ref "C83") (pin "2") (pinfunction "2_2") (pintype "passive"))
      (node (ref "U31") (pin "2") (pinfunction "VDD_2") (pintype "power_in"))
    )
    (net (code "57") (name "Net-(U31-VEE)") (class "Default")
      (node (ref "C90") (pin "2") (pinfunction "2_2") (pintype "passive"))
      (node (ref "U31") (pin "6") (pinfunction "VEE_6") (pintype "power_in"))
    )
    (net (code "58") (name "Net-(U33-VIB)") (class "Default")
      (node (ref "R97") (pin "1") (pinfunction "1_1") (pintype "passive"))
      (node (ref "U33") (pin "3") (pinfunction "VIB_3") (pintype "passive"))
    )
    (net (code "59") (name "Net-(U33-VOA)") (class "Default")
      (node (ref "R96") (pin "2") (pinfunction "2_2") (pintype "passive"))
      (node (ref "U33") (pin "2") (pinfunction "VOA_2") (pintype "passive"))
    )
    (net (code "60") (name "Net-(U34-C1+)") (class "Default")
      (node (ref "C92") (pin "1") (pinfunction "1_1") (pintype "passive"))
      (node (ref "U34") (pin "1") (pinfunction "C1+_1") (pintype "passive"))
    )
    (net (code "61") (name "Net-(U34-C1-)") (class "Default")
      (node (ref "C92") (pin "2") (pinfunction "2_2") (pintype "passive"))
      (node (ref "U34") (pin "3") (pinfunction "C1-_3") (pintype "passive"))
    )
    (net (code "62") (name "Net-(U34-C2+)") (class "Default")
      (node (ref "C94") (pin "2") (pinfunction "2_2") (pintype "passive"))
      (node (ref "U34") (pin "4") (pinfunction "C2+_4") (pintype "passive"))
    )
    (net (code "63") (name "Net-(U34-C2-)") (class "Default")
      (node (ref "C94") (pin "1") (pinfunction "1_1") (pintype "passive"))
      (node (ref "U34") (pin "5") (pinfunction "C2-_5") (pintype "passive"))
    )
    (net (code "64") (name "Net-(U34-R1IN)") (class "Default")
      (node (ref "R100") (pin "2") (pinfunction "2_2") (pintype "passive"))
      (node (ref "U34") (pin "13") (pinfunction "R1IN_13") (pintype "input"))
    )
    (net (code "65") (name "Net-(U34-T1IN)") (class "Default")
      (node (ref "U34") (pin "11") (pinfunction "T1IN_11") (pintype "input"))
      (node (ref "U36") (pin "6") (pinfunction "VOB_6") (pintype "passive"))
      (node (ref "U37") (pin "4") (pinfunction "DI_4") (pintype "input"))
    )
    (net (code "66") (name "Net-(U34-T1OUT)") (class "Default")
      (node (ref "R99") (pin "2") (pinfunction "2_2") (pintype "passive"))
      (node (ref "U34") (pin "14") (pinfunction "T1OUT_14") (pintype "output"))
    )
    (net (code "67") (name "Net-(U34-VDD)") (class "Default")
      (node (ref "C93") (pin "2") (pinfunction "2_2") (pintype "passive"))
      (node (ref "U34") (pin "2") (pinfunction "VDD_2") (pintype "power_in"))
    )
    (net (code "68") (name "Net-(U34-VEE)") (class "Default")
      (node (ref "C97") (pin "2") (pinfunction "2_2") (pintype "passive"))
      (node (ref "U34") (pin "6") (pinfunction "VEE_6") (pintype "power_in"))
    )
    (net (code "69") (name "Net-(U36-VIB)") (class "Default")
      (node (ref "R102") (pin "1") (pinfunction "1_1") (pintype "passive"))
      (node (ref "U36") (pin "3") (pinfunction "VIB_3") (pintype "passive"))
    )
    (net (code "70") (name "Net-(U36-VOA)") (class "Default")
      (node (ref "R101") (pin "2") (pinfunction "2_2") (pintype "passive"))
      (node (ref "U36") (pin "2") (pinfunction "VOA_2") (pintype "passive"))
    )
    (net (code "71") (name "Net-(U37-DE)") (class "Default")
      (node (ref "R107") (pin "1") (pinfunction "1_1") (pintype "passive"))
      (node (ref "U37") (pin "2") (pinfunction "~{RE}_2") (pintype "input"))
      (node (ref "U37") (pin "3") (pinfunction "DE_3") (pintype "input"))
      (node (ref "U38") (pin "3") (pinfunction "E_3") (pintype "passive"))
    )
    (net (code "72") (name "Net-(U38-K)") (class "Default")
      (node (ref "R105") (pin "2") (pinfunction "2_2") (pintype "passive"))
      (node (ref "U38") (pin "2") (pinfunction "K_2") (pintype "passive"))
    )
    (net (code "73") (name "RS5V1") (class "Default")
      (node (ref "C72") (pin "1") (pinfunction "1_1") (pintype "passive"))
      (node (ref "C74") (pin "1") (pinfunction "1_1") (pintype "passive"))
      (node (ref "C75") (pin "1") (pinfunction "1_1") (pintype "passive"))
      (node (ref "C78") (pin "1") (pinfunction "1_1") (pintype "passive"))
      (node (ref "C79") (pin "2") (pinfunction "2_2") (pintype "passive"))
      (node (ref "U27") (pin "1") (pinfunction "A_1") (pintype "passive"))
      (node (ref "U28") (pin "16") (pinfunction "VCC_16") (pintype "power_in"))
      (node (ref "U29") (pin "4") (pinfunction "+Vo_4") (pintype "passive"))
      (node (ref "U30") (pin "8") (pinfunction "VDD2_8") (pintype "passive"))
    )
    (net (code "74") (name "RS5V2") (class "Default")
      (node (ref "C83") (pin "1") (pinfunction "1_1") (pintype "passive"))
      (node (ref "C85") (pin "1") (pinfunction "1_1") (pintype "passive"))
      (node (ref "C86") (pin "1") (pinfunction "1_1") (pintype "passive"))
      (node (ref "C88") (pin "1") (pinfunction "1_1") (pintype "passive"))
      (node (ref "C89") (pin "2") (pinfunction "2_2") (pintype "passive"))
      (node (ref "U31") (pin "16") (pinfunction "VCC_16") (pintype "power_in"))
      (node (ref "U32") (pin "4") (pinfunction "+Vo_4") (pintype "passive"))
      (node (ref "U33") (pin "8") (pinfunction "VDD2_8") (pintype "passive"))
    )
    (net (code "75") (name "RS5V3") (class "Default")
      (node (ref "C100") (pin "1") (pinfunction "1_1") (pintype "passive"))
      (node (ref "C101") (pin "2") (pinfunction "2_2") (pintype "passive"))
      (node (ref "C102") (pin "2") (pinfunction "2_2") (pintype "passive"))
      (node (ref "C93") (pin "1") (pinfunction "1_1") (pintype "passive"))
      (node (ref "C95") (pin "1") (pinfunction "1_1") (pintype "passive"))
      (node (ref "C96") (pin "1") (pinfunction "1_1") (pintype "passive"))
      (node (ref "R104") (pin "1") (pinfunction "1_1") (pintype "passive"))
      (node (ref "U34") (pin "16") (pinfunction "VCC_16") (pintype "power_in"))
      (node (ref "U35") (pin "4") (pinfunction "+Vo_4") (pintype "passive"))
      (node (ref "U36") (pin "8") (pinfunction "VDD2_8") (pintype "passive"))
      (node (ref "U37") (pin "8") (pinfunction "VCC_8") (pintype "power_in"))
      (node (ref "U38") (pin "4") (pinfunction "C_4") (pintype "passive"))
    )
    (net (code "76") (name "VCC3V3") (class "Default")
      (node (ref "U27") (pin "4") (pinfunction "C_4") (pintype "passive"))
      (node (ref "U30") (pin "1") (pinfunction "VDD1_1") (pintype "passive"))
      (node (ref "U33") (pin "1") (pinfunction "VDD1_1") (pintype "passive"))
      (node (ref "U36") (pin "1") (pinfunction "VDD1_1") (pintype "passive"))
      (node (ref "U38") (pin "1") (pinfunction "A_1") (pintype "passive"))
    )
    (net (code "77") (name "VCC5V") (class "Default")
      (node (ref "C76") (pin "2") (pinfunction "2_2") (pintype "passive"))
      (node (ref "C77") (pin "1") (pinfunction "1_1") (pintype "passive"))
      (node (ref "C87") (pin "1") (pinfunction "1_1") (pintype "passive"))
      (node (ref "C99") (pin "1") (pinfunction "1_1") (pintype "passive"))
      (node (ref "U29") (pin "2") (pinfunction "Vin_2") (pintype "passive"))
      (node (ref "U32") (pin "2") (pinfunction "Vin_2") (pintype "passive"))
      (node (ref "U35") (pin "2") (pinfunction "Vin_2") (pintype "passive"))
    )
    (net (code "78") (name "unconnected-(P13-Pad1)") (class "Default")
      (node (ref "P13") (pin "1") (pinfunction "1_1") (pintype "passive"))
    )
    (net (code "79") (name "unconnected-(P13-Pad6)") (class "Default")
      (node (ref "P13") (pin "6") (pinfunction "6_6") (pintype "passive"))
    )
    (net (code "80") (name "unconnected-(P13-Pad7)") (class "Default")
      (node (ref "P13") (pin "7") (pinfunction "7_7") (pintype "passive"))
    )
    (net (code "81") (name "unconnected-(P13-Pad8)") (class "Default")
      (node (ref "P13") (pin "8") (pinfunction "8_8") (pintype "passive"))
    )
    (net (code "82") (name "unconnected-(P13-Pad9)") (class "Default")
      (node (ref "P13") (pin "9") (pinfunction "9_9") (pintype "passive"))
    )
    (net (code "83") (name "unconnected-(U28-T1OUT-Pad14)") (class "Default")
      (node (ref "U28") (pin "14") (pinfunction "T1OUT_14") (pintype "output"))
    )
    (net (code "84") (name "unconnected-(U31-R2OUT-Pad9)") (class "Default")
      (node (ref "U31") (pin "9") (pinfunction "R2OUT_9") (pintype "output"))
    )
    (net (code "85") (name "unconnected-(U31-T2OUT-Pad7)") (class "Default")
      (node (ref "U31") (pin "7") (pinfunction "T2OUT_7") (pintype "output"))
    )
    (net (code "86") (name "unconnected-(U34-R2OUT-Pad9)") (class "Default")
      (node (ref "U34") (pin "9") (pinfunction "R2OUT_9") (pintype "output"))
    )
    (net (code "87") (name "unconnected-(U34-T2OUT-Pad7)") (class "Default")
      (node (ref "U34") (pin "7") (pinfunction "T2OUT_7") (pintype "output"))
    )
  )
)
